# POV2_2.net
KiCad netlist of a schematic drawn in EAGLE
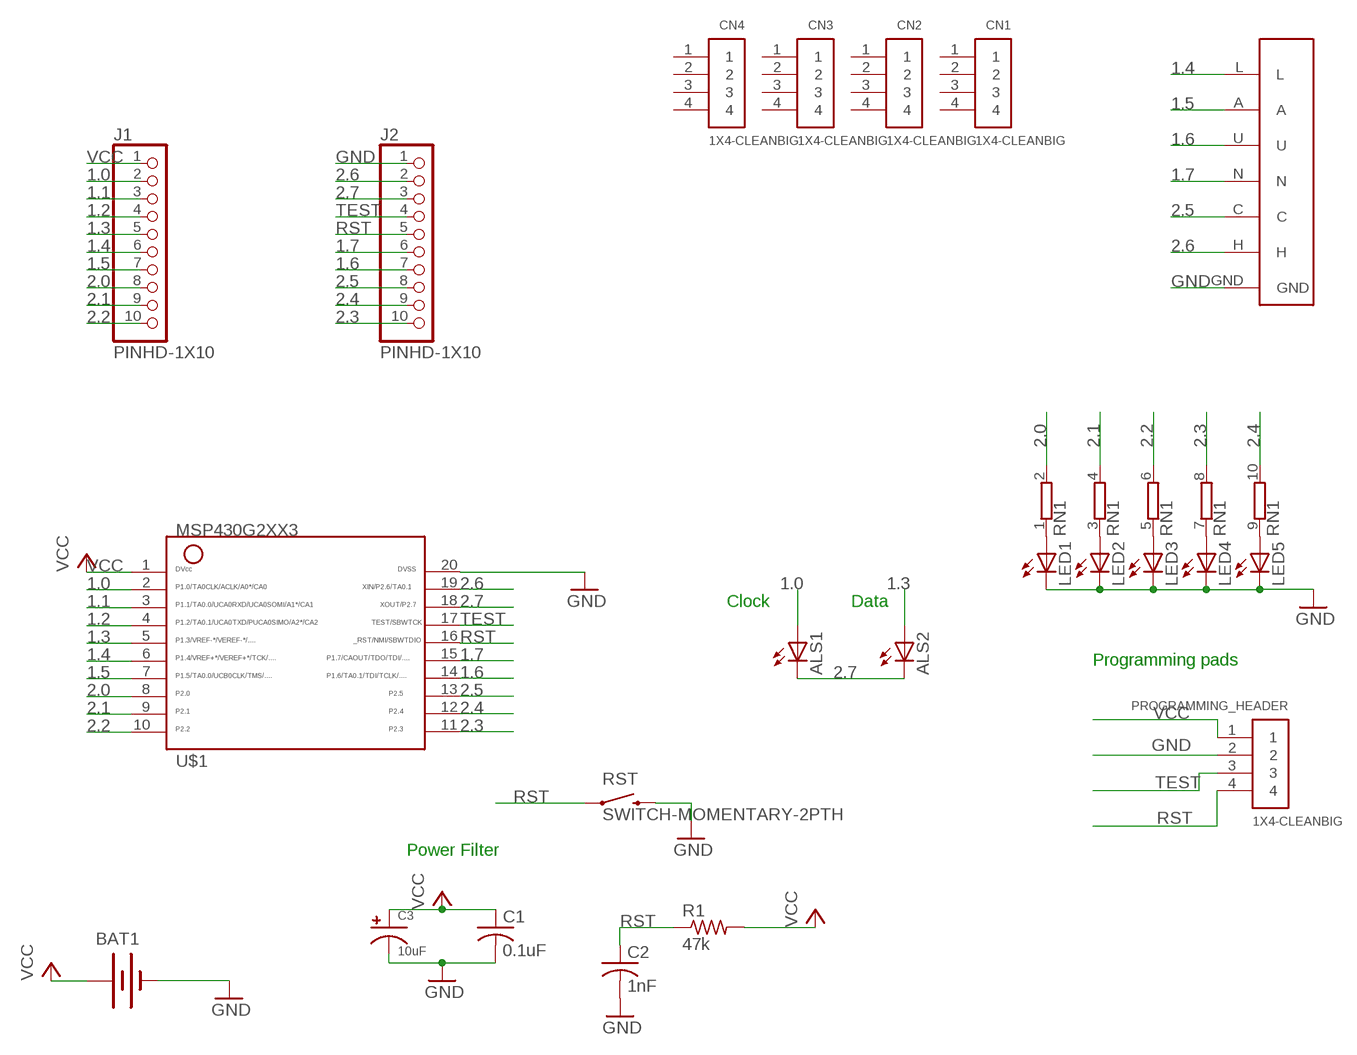
[diagram p0: schematic, sheet 1]

(export (version "E")
  (design (tool "Eeschema 10.0.6"))
  (components
    (comp (ref "ALS1")
      (value "LED3MM")
      (footprint "eagle-import:LED3MM")
      (libsource (lib "eagle-import") (part "LED3MM"))
    )
    (comp (ref "ALS2")
      (value "LED3MM")
      (footprint "eagle-import:LED3MM")
      (libsource (lib "eagle-import") (part "LED3MM"))
    )
    (comp (ref "BAT1")
      (value "BATTERYELECROW_2032_BATTERY_HOLDER")
      (footprint "eagle-import:BATTCON_20MM_4LEGS")
      (libsource (lib "eagle-import") (part "BATTERYELECROW_2032_BATTERY_HOLDER"))
    )
    (comp (ref "C1")
      (value "0.1uF")
      (footprint "eagle-import:C025-024X044")
      (libsource (lib "eagle-import") (part "C-US025-024X044"))
    )
    (comp (ref "C2")
      (value "1nF")
      (footprint "eagle-import:C025-024X044")
      (libsource (lib "eagle-import") (part "C-US025-024X044"))
    )
    (comp (ref "C3")
      (value "10uF")
      (footprint "eagle-import:E2,5-5")
      (libsource (lib "eagle-import") (part "CPOL-US"))
    )
    (comp (ref "CN1")
      (value "1X4-CLEANBIG")
      (footprint "eagle-import:1X04-CLEANBIG")
      (libsource (lib "eagle-import") (part "adafruit_1X4-CLEANBIG"))
    )
    (comp (ref "CN2")
      (value "1X4-CLEANBIG")
      (footprint "eagle-import:1X04-CLEANBIG")
      (libsource (lib "eagle-import") (part "adafruit_1X4-CLEANBIG"))
    )
    (comp (ref "CN3")
      (value "1X4-CLEANBIG")
      (footprint "eagle-import:1X04-CLEANBIG")
      (libsource (lib "eagle-import") (part "adafruit_1X4-CLEANBIG"))
    )
    (comp (ref "CN4")
      (value "1X4-CLEANBIG")
      (footprint "eagle-import:1X04-CLEANBIG")
      (libsource (lib "eagle-import") (part "adafruit_1X4-CLEANBIG"))
    )
    (comp (ref "J1")
      (value "PINHD-1X10")
      (footprint "eagle-import:1X10-BIG")
      (libsource (lib "eagle-import") (part "PINHD-1X10"))
    )
    (comp (ref "J2")
      (value "PINHD-1X10")
      (footprint "eagle-import:1X10-BIG")
      (libsource (lib "eagle-import") (part "PINHD-1X10"))
    )
    (comp (ref "LED1")
      (value "LED3MM")
      (footprint "eagle-import:LED3MM")
      (libsource (lib "eagle-import") (part "LED3MM"))
    )
    (comp (ref "LED2")
      (value "LED3MM")
      (footprint "eagle-import:LED3MM")
      (libsource (lib "eagle-import") (part "LED3MM"))
    )
    (comp (ref "LED3")
      (value "LED3MM")
      (footprint "eagle-import:LED3MM")
      (libsource (lib "eagle-import") (part "LED3MM"))
    )
    (comp (ref "LED4")
      (value "LED3MM")
      (footprint "eagle-import:LED3MM")
      (libsource (lib "eagle-import") (part "LED3MM"))
    )
    (comp (ref "LED5")
      (value "LED3MM")
      (footprint "eagle-import:LED3MM")
      (libsource (lib "eagle-import") (part "LED3MM"))
    )
    (comp (ref "PROGRAMMING_HEADER")
      (value "1X4-CLEANBIG")
      (footprint "eagle-import:1X04-CLEANBIG")
      (libsource (lib "eagle-import") (part "1X4-CLEANBIG"))
    )
    (comp (ref "R1")
      (value "47k")
      (footprint "eagle-import:0204_7")
      (libsource (lib "eagle-import") (part "R-US_0204/7"))
    )
    (comp (ref "RN1")
      (value "E5RP")
      (footprint "eagle-import:SIL10")
      (libsource (lib "eagle-import") (part "E5RP"))
    )
    (comp (ref "RST")
      (value "SWITCH-MOMENTARY-2PTH")
      (footprint "eagle-import:TACTILE-PTH")
      (libsource (lib "eagle-import") (part "SWITCH-MOMENTARY-2PTH"))
    )
    (comp (ref "U$1")
      (value "G2553")
      (footprint "eagle-import:N20")
      (libsource (lib "eagle-import") (part "G2XX3---N20"))
    )
    (comp (ref "U$5")
      (value "LAUNCH_SLIDER")
      (footprint "eagle-import:LAUNCHYOURDESIGN_CAPT_SLIDER")
      (libsource (lib "eagle-import") (part "LAUNCH_SLIDER"))
    )
  )
  (nets
    (net (code "1") (name "/1.0") (class "Default")
      (node (ref "ALS1") (pin "A") (pinfunction "A_A") (pintype "passive"))
      (node (ref "J1") (pin "2") (pinfunction "2_2") (pintype "passive"))
      (node (ref "U$1") (pin "2") (pinfunction "2_2") (pintype "bidirectional"))
    )
    (net (code "2") (name "/1.1") (class "Default")
      (node (ref "J1") (pin "3") (pinfunction "3_3") (pintype "passive"))
      (node (ref "U$1") (pin "3") (pinfunction "3_3") (pintype "bidirectional"))
    )
    (net (code "3") (name "/1.2") (class "Default")
      (node (ref "J1") (pin "4") (pinfunction "4_4") (pintype "passive"))
      (node (ref "U$1") (pin "4") (pinfunction "4_4") (pintype "bidirectional"))
    )
    (net (code "4") (name "/1.3") (class "Default")
      (node (ref "ALS2") (pin "A") (pinfunction "A_A") (pintype "passive"))
      (node (ref "J1") (pin "5") (pinfunction "5_5") (pintype "passive"))
      (node (ref "U$1") (pin "5") (pinfunction "5_5") (pintype "bidirectional"))
    )
    (net (code "5") (name "/1.4") (class "Default")
      (node (ref "J1") (pin "6") (pinfunction "6_6") (pintype "passive"))
      (node (ref "U$1") (pin "6") (pinfunction "6_6") (pintype "bidirectional"))
      (node (ref "U$5") (pin "L") (pinfunction "L_L") (pintype "bidirectional"))
    )
    (net (code "6") (name "/1.5") (class "Default")
      (node (ref "J1") (pin "7") (pinfunction "7_7") (pintype "passive"))
      (node (ref "U$1") (pin "7") (pinfunction "7_7") (pintype "bidirectional"))
      (node (ref "U$5") (pin "A") (pinfunction "A_A") (pintype "bidirectional"))
    )
    (net (code "7") (name "/1.6") (class "Default")
      (node (ref "J2") (pin "7") (pinfunction "7_7") (pintype "passive"))
      (node (ref "U$1") (pin "14") (pinfunction "14_14") (pintype "bidirectional"))
      (node (ref "U$5") (pin "U") (pinfunction "U_U") (pintype "bidirectional"))
    )
    (net (code "8") (name "/1.7") (class "Default")
      (node (ref "J2") (pin "6") (pinfunction "6_6") (pintype "passive"))
      (node (ref "U$1") (pin "15") (pinfunction "15_15") (pintype "bidirectional"))
      (node (ref "U$5") (pin "N") (pinfunction "N_N") (pintype "bidirectional"))
    )
    (net (code "9") (name "/2.0") (class "Default")
      (node (ref "J1") (pin "8") (pinfunction "8_8") (pintype "passive"))
      (node (ref "RN1") (pin "2") (pinfunction "2_2") (pintype "passive"))
      (node (ref "U$1") (pin "8") (pinfunction "8_8") (pintype "bidirectional"))
    )
    (net (code "10") (name "/2.1") (class "Default")
      (node (ref "J1") (pin "9") (pinfunction "9_9") (pintype "passive"))
      (node (ref "RN1") (pin "4") (pinfunction "2_4") (pintype "passive"))
      (node (ref "U$1") (pin "9") (pinfunction "9_9") (pintype "bidirectional"))
    )
    (net (code "11") (name "/2.2") (class "Default")
      (node (ref "J1") (pin "10") (pinfunction "10_10") (pintype "passive"))
      (node (ref "RN1") (pin "6") (pinfunction "2_6") (pintype "passive"))
      (node (ref "U$1") (pin "10") (pinfunction "10_10") (pintype "bidirectional"))
    )
    (net (code "12") (name "/2.3") (class "Default")
      (node (ref "J2") (pin "10") (pinfunction "10_10") (pintype "passive"))
      (node (ref "RN1") (pin "8") (pinfunction "2_8") (pintype "passive"))
      (node (ref "U$1") (pin "11") (pinfunction "11_11") (pintype "bidirectional"))
    )
    (net (code "13") (name "/2.4") (class "Default")
      (node (ref "J2") (pin "9") (pinfunction "9_9") (pintype "passive"))
      (node (ref "RN1") (pin "10") (pinfunction "2_10") (pintype "passive"))
      (node (ref "U$1") (pin "12") (pinfunction "12_12") (pintype "bidirectional"))
    )
    (net (code "14") (name "/2.5") (class "Default")
      (node (ref "J2") (pin "8") (pinfunction "8_8") (pintype "passive"))
      (node (ref "U$1") (pin "13") (pinfunction "13_13") (pintype "bidirectional"))
      (node (ref "U$5") (pin "C") (pinfunction "C_C") (pintype "bidirectional"))
    )
    (net (code "15") (name "/2.6") (class "Default")
      (node (ref "J2") (pin "2") (pinfunction "2_2") (pintype "passive"))
      (node (ref "U$1") (pin "19") (pinfunction "19_19") (pintype "bidirectional"))
      (node (ref "U$5") (pin "H") (pinfunction "H_H") (pintype "bidirectional"))
    )
    (net (code "16") (name "/2.7") (class "Default")
      (node (ref "ALS1") (pin "K") (pinfunction "C_K") (pintype "passive"))
      (node (ref "ALS2") (pin "K") (pinfunction "C_K") (pintype "passive"))
      (node (ref "J2") (pin "3") (pinfunction "3_3") (pintype "passive"))
      (node (ref "U$1") (pin "18") (pinfunction "18_18") (pintype "bidirectional"))
    )
    (net (code "17") (name "/RST") (class "Default")
      (node (ref "C2") (pin "1") (pinfunction "1_1") (pintype "passive"))
      (node (ref "J2") (pin "5") (pinfunction "5_5") (pintype "passive"))
      (node (ref "PROGRAMMING_HEADER") (pin "4") (pinfunction "4_4") (pintype "bidirectional"))
      (node (ref "R1") (pin "1") (pinfunction "1_1") (pintype "passive"))
      (node (ref "RST") (pin "1") (pinfunction "1_1") (pintype "passive"))
      (node (ref "RST") (pin "2") (pinfunction "1_2") (pintype "passive"))
      (node (ref "U$1") (pin "16") (pinfunction "16_16") (pintype "bidirectional"))
    )
    (net (code "18") (name "/TEST") (class "Default")
      (node (ref "J2") (pin "4") (pinfunction "4_4") (pintype "passive"))
      (node (ref "PROGRAMMING_HEADER") (pin "3") (pinfunction "3_3") (pintype "bidirectional"))
      (node (ref "U$1") (pin "17") (pinfunction "17_17") (pintype "bidirectional"))
    )
    (net (code "19") (name "GND") (class "Default")
      (node (ref "BAT1") (pin "GND") (pinfunction "-_GND") (pintype "power_in"))
      (node (ref "C1") (pin "2") (pinfunction "2_2") (pintype "passive"))
      (node (ref "C2") (pin "2") (pinfunction "2_2") (pintype "passive"))
      (node (ref "C3") (pin "-") (pinfunction "-_-") (pintype "bidirectional"))
      (node (ref "J2") (pin "1") (pinfunction "1_1") (pintype "passive"))
      (node (ref "LED1") (pin "K") (pinfunction "C_K") (pintype "passive"))
      (node (ref "LED2") (pin "K") (pinfunction "C_K") (pintype "passive"))
      (node (ref "LED3") (pin "K") (pinfunction "C_K") (pintype "passive"))
      (node (ref "LED4") (pin "K") (pinfunction "C_K") (pintype "passive"))
      (node (ref "LED5") (pin "K") (pinfunction "C_K") (pintype "passive"))
      (node (ref "PROGRAMMING_HEADER") (pin "2") (pinfunction "2_2") (pintype "bidirectional"))
      (node (ref "RST") (pin "3") (pinfunction "2_3") (pintype "passive"))
      (node (ref "RST") (pin "4") (pinfunction "2_4") (pintype "passive"))
      (node (ref "U$1") (pin "20") (pinfunction "20_20") (pintype "bidirectional"))
      (node (ref "U$5") (pin "GND") (pinfunction "GND_GND") (pintype "bidirectional"))
    )
    (net (code "20") (name "Net-(LED1-PadA)") (class "Default")
      (node (ref "LED1") (pin "A") (pinfunction "A_A") (pintype "passive"))
      (node (ref "RN1") (pin "1") (pinfunction "1_1") (pintype "passive"))
    )
    (net (code "21") (name "Net-(RN1B-1)") (class "Default")
      (node (ref "LED2") (pin "A") (pinfunction "A_A") (pintype "passive"))
      (node (ref "RN1") (pin "3") (pinfunction "1_3") (pintype "passive"))
    )
    (net (code "22") (name "Net-(RN1C-1)") (class "Default")
      (node (ref "LED3") (pin "A") (pinfunction "A_A") (pintype "passive"))
      (node (ref "RN1") (pin "5") (pinfunction "1_5") (pintype "passive"))
    )
    (net (code "23") (name "Net-(RN1D-1)") (class "Default")
      (node (ref "LED4") (pin "A") (pinfunction "A_A") (pintype "passive"))
      (node (ref "RN1") (pin "7") (pinfunction "1_7") (pintype "passive"))
    )
    (net (code "24") (name "Net-(RN1E-1)") (class "Default")
      (node (ref "LED5") (pin "A") (pinfunction "A_A") (pintype "passive"))
      (node (ref "RN1") (pin "9") (pinfunction "1_9") (pintype "passive"))
    )
    (net (code "25") (name "VCC") (class "Default")
      (node (ref "BAT1") (pin "VCC1") (pinfunction "+_VCC1") (pintype "power_in"))
      (node (ref "BAT1") (pin "VCC2") (pinfunction "+_VCC2") (pintype "power_in"))
      (node (ref "C1") (pin "1") (pinfunction "1_1") (pintype "passive"))
      (node (ref "C3") (pin "+") (pinfunction "+_+") (pintype "bidirectional"))
      (node (ref "J1") (pin "1") (pinfunction "1_1") (pintype "passive"))
      (node (ref "PROGRAMMING_HEADER") (pin "1") (pinfunction "1_1") (pintype "bidirectional"))
      (node (ref "R1") (pin "2") (pinfunction "2_2") (pintype "passive"))
      (node (ref "U$1") (pin "1") (pinfunction "1_1") (pintype "bidirectional"))
    )
    (net (code "26") (name "unconnected-(CN1-Pad1)") (class "Default")
      (node (ref "CN1") (pin "1") (pinfunction "1_1") (pintype "bidirectional"))
    )
    (net (code "27") (name "unconnected-(CN1-Pad2)") (class "Default")
      (node (ref "CN1") (pin "2") (pinfunction "2_2") (pintype "bidirectional"))
    )
    (net (code "28") (name "unconnected-(CN1-Pad3)") (class "Default")
      (node (ref "CN1") (pin "3") (pinfunction "3_3") (pintype "bidirectional"))
    )
    (net (code "29") (name "unconnected-(CN1-Pad4)") (class "Default")
      (node (ref "CN1") (pin "4") (pinfunction "4_4") (pintype "bidirectional"))
    )
    (net (code "30") (name "unconnected-(CN2-Pad1)") (class "Default")
      (node (ref "CN2") (pin "1") (pinfunction "1_1") (pintype "bidirectional"))
    )
    (net (code "31") (name "unconnected-(CN2-Pad2)") (class "Default")
      (node (ref "CN2") (pin "2") (pinfunction "2_2") (pintype "bidirectional"))
    )
    (net (code "32") (name "unconnected-(CN2-Pad3)") (class "Default")
      (node (ref "CN2") (pin "3") (pinfunction "3_3") (pintype "bidirectional"))
    )
    (net (code "33") (name "unconnected-(CN2-Pad4)") (class "Default")
      (node (ref "CN2") (pin "4") (pinfunction "4_4") (pintype "bidirectional"))
    )
    (net (code "34") (name "unconnected-(CN3-Pad1)") (class "Default")
      (node (ref "CN3") (pin "1") (pinfunction "1_1") (pintype "bidirectional"))
    )
    (net (code "35") (name "unconnected-(CN3-Pad2)") (class "Default")
      (node (ref "CN3") (pin "2") (pinfunction "2_2") (pintype "bidirectional"))
    )
    (net (code "36") (name "unconnected-(CN3-Pad3)") (class "Default")
      (node (ref "CN3") (pin "3") (pinfunction "3_3") (pintype "bidirectional"))
    )
    (net (code "37") (name "unconnected-(CN3-Pad4)") (class "Default")
      (node (ref "CN3") (pin "4") (pinfunction "4_4") (pintype "bidirectional"))
    )
    (net (code "38") (name "unconnected-(CN4-Pad1)") (class "Default")
      (node (ref "CN4") (pin "1") (pinfunction "1_1") (pintype "bidirectional"))
    )
    (net (code "39") (name "unconnected-(CN4-Pad2)") (class "Default")
      (node (ref "CN4") (pin "2") (pinfunction "2_2") (pintype "bidirectional"))
    )
    (net (code "40") (name "unconnected-(CN4-Pad3)") (class "Default")
      (node (ref "CN4") (pin "3") (pinfunction "3_3") (pintype "bidirectional"))
    )
    (net (code "41") (name "unconnected-(CN4-Pad4)") (class "Default")
      (node (ref "CN4") (pin "4") (pinfunction "4_4") (pintype "bidirectional"))
    )
  )
)
